# sensorCorrente_rev1_0.net
KiCad netlist of a schematic drawn in EAGLE
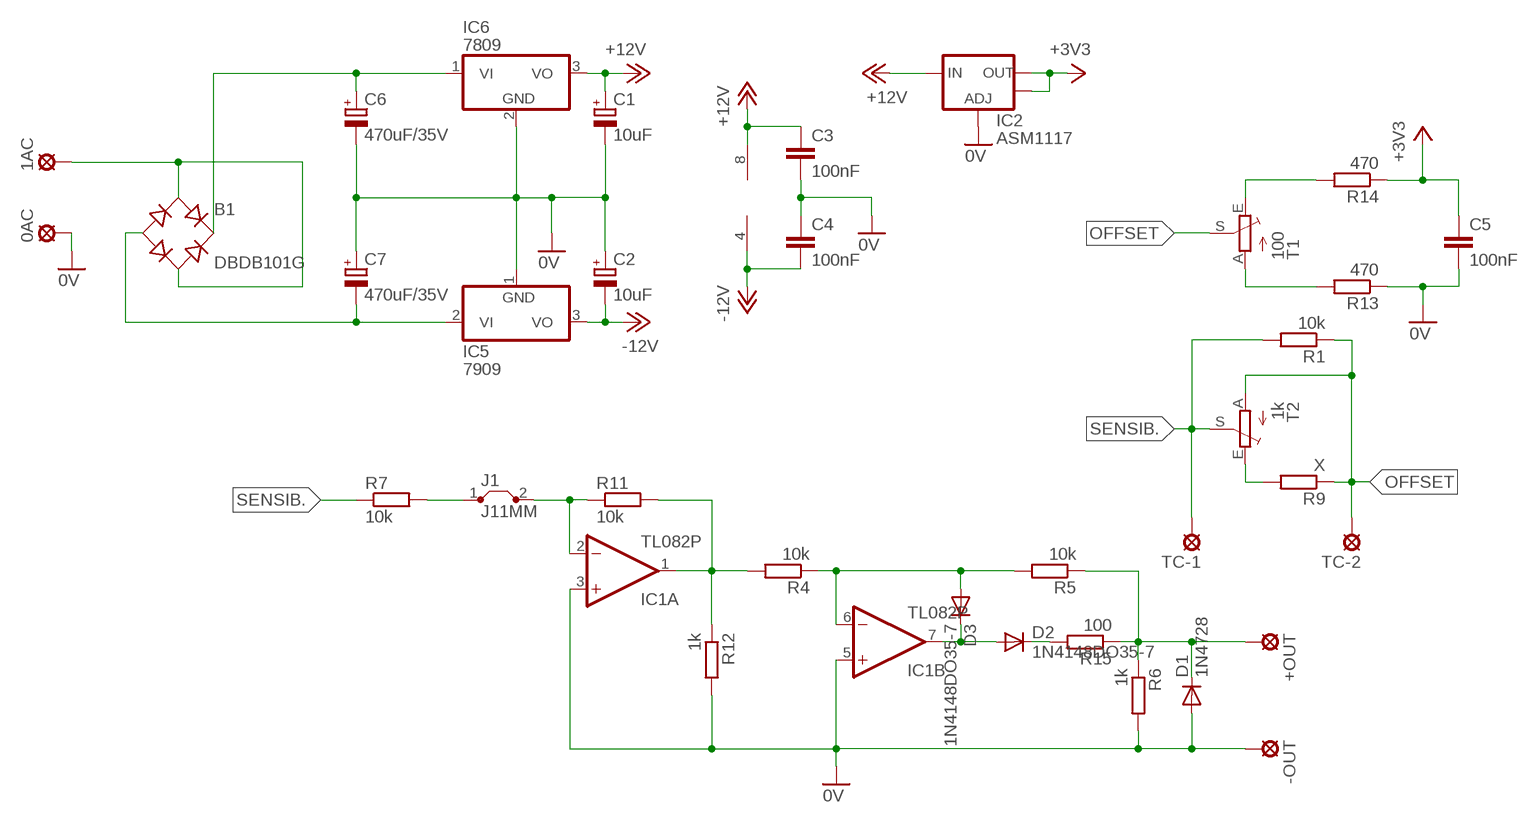
[diagram p0: schematic, sheet 1]

(export (version "E")
  (design (tool "Eeschema 10.0.6"))
  (components
    (comp (ref "+OUT")
      (value "+D")
      (footprint "eagle-import:LSP10")
      (libsource (lib "eagle-import") (part "LSP10"))
    )
    (comp (ref "-OUT")
      (value "0V")
      (footprint "eagle-import:LSP10")
      (libsource (lib "eagle-import") (part "LSP10"))
    )
    (comp (ref "0AC")
      (value "0V")
      (footprint "eagle-import:LSP10")
      (libsource (lib "eagle-import") (part "LSP10"))
    )
    (comp (ref "1AC")
      (value "AC")
      (footprint "eagle-import:LSP10")
      (libsource (lib "eagle-import") (part "LSP10"))
    )
    (comp (ref "B1")
      (value "DBDB101G")
      (footprint "eagle-import:DB")
      (libsource (lib "eagle-import") (part "DB?GDB101"))
    )
    (comp (ref "C1")
      (value "10uF")
      (footprint "eagle-import:E2,5-7")
      (libsource (lib "eagle-import") (part "CPOL-EUE2.5-7"))
    )
    (comp (ref "C2")
      (value "10uF")
      (footprint "eagle-import:E2,5-7")
      (libsource (lib "eagle-import") (part "CPOL-EUE2.5-7"))
    )
    (comp (ref "C3")
      (value "100nF")
      (footprint "eagle-import:C050-024X044")
      (libsource (lib "eagle-import") (part "C-EU050-024X044"))
    )
    (comp (ref "C4")
      (value "100nF")
      (footprint "eagle-import:C050-024X044")
      (libsource (lib "eagle-import") (part "C-EU050-024X044"))
    )
    (comp (ref "C5")
      (value "100nF")
      (footprint "eagle-import:C050-024X044")
      (libsource (lib "eagle-import") (part "C-EU050-024X044"))
    )
    (comp (ref "C6")
      (value "470uF/35V")
      (footprint "eagle-import:E3,5-10")
      (libsource (lib "eagle-import") (part "CPOL-EUE3.5-10"))
    )
    (comp (ref "C7")
      (value "470uF/35V")
      (footprint "eagle-import:E3,5-10")
      (libsource (lib "eagle-import") (part "CPOL-EUE3.5-10"))
    )
    (comp (ref "D1")
      (value "1N4728")
      (footprint "eagle-import:DO35-7")
      (libsource (lib "eagle-import") (part "1N4148DO35-7"))
    )
    (comp (ref "D2")
      (value "1N4148DO35-7")
      (footprint "eagle-import:DO35-7")
      (libsource (lib "eagle-import") (part "1N4148DO35-7"))
    )
    (comp (ref "D3")
      (value "1N4148DO35-7")
      (footprint "eagle-import:DO35-7")
      (libsource (lib "eagle-import") (part "1N4148DO35-7"))
    )
    (comp (ref "IC1")
      (value "TL082P")
      (footprint "eagle-import:DIL08")
      (libsource (lib "eagle-import") (part "TL082P"))
    )
    (comp (ref "IC2")
      (value "ASM1117")
      (footprint "eagle-import:SOT223")
      (libsource (lib "eagle-import") (part "V_REG_LM1117SOT223"))
    )
    (comp (ref "IC5")
      (value "7909")
      (footprint "eagle-import:TO220V")
      (libsource (lib "eagle-import") (part "7912"))
    )
    (comp (ref "IC6")
      (value "7809")
      (footprint "eagle-import:TO220V")
      (libsource (lib "eagle-import") (part "78TV12"))
    )
    (comp (ref "J1")
      (value "J11MM")
      (footprint "eagle-import:11")
      (libsource (lib "eagle-import") (part "J11MM"))
    )
    (comp (ref "R1")
      (value "10k")
      (footprint "eagle-import:0204_7")
      (libsource (lib "eagle-import") (part "R-EU_0204/7"))
    )
    (comp (ref "R4")
      (value "10k")
      (footprint "eagle-import:0204_7")
      (libsource (lib "eagle-import") (part "R-EU_0204/7"))
    )
    (comp (ref "R5")
      (value "10k")
      (footprint "eagle-import:0204_10")
      (libsource (lib "eagle-import") (part "R-EU_0204/10"))
    )
    (comp (ref "R6")
      (value "1k")
      (footprint "eagle-import:0204_7")
      (libsource (lib "eagle-import") (part "R-EU_0204/7"))
    )
    (comp (ref "R7")
      (value "10k")
      (footprint "eagle-import:0204_7")
      (libsource (lib "eagle-import") (part "R-EU_0204/7"))
    )
    (comp (ref "R9")
      (value "X")
      (footprint "eagle-import:0204_7")
      (libsource (lib "eagle-import") (part "R-EU_0204/7"))
    )
    (comp (ref "R11")
      (value "10k")
      (footprint "eagle-import:0204_7")
      (libsource (lib "eagle-import") (part "R-EU_0204/7"))
    )
    (comp (ref "R12")
      (value "1k")
      (footprint "eagle-import:0204_7")
      (libsource (lib "eagle-import") (part "R-EU_0204/7"))
    )
    (comp (ref "R13")
      (value "470")
      (footprint "eagle-import:0204_7")
      (libsource (lib "eagle-import") (part "R-EU_0204/7"))
    )
    (comp (ref "R14")
      (value "470")
      (footprint "eagle-import:0204_7")
      (libsource (lib "eagle-import") (part "R-EU_0204/7"))
    )
    (comp (ref "R15")
      (value "100")
      (footprint "eagle-import:0204_7")
      (libsource (lib "eagle-import") (part "R-EU_0204/7"))
    )
    (comp (ref "T1")
      (value "100")
      (footprint "eagle-import:CA6V")
      (libsource (lib "eagle-import") (part "TRIM_EU-CA6V"))
    )
    (comp (ref "T2")
      (value "1k")
      (footprint "eagle-import:CA6V")
      (libsource (lib "eagle-import") (part "TRIM_EU-CA6V"))
    )
    (comp (ref "TC-1")
      (value "AC")
      (footprint "eagle-import:LSP10")
      (libsource (lib "eagle-import") (part "LSP10"))
    )
    (comp (ref "TC-2")
      (value "AC")
      (footprint "eagle-import:LSP10")
      (libsource (lib "eagle-import") (part "LSP10"))
    )
  )
  (nets
    (net (code "1") (name "+3V3") (class "Default")
      (node (ref "C5") (pin "1") (pinfunction "1_1") (pintype "passive"))
      (node (ref "IC2") (pin "2") (pinfunction "OUT_2") (pintype "output"))
      (node (ref "IC2") (pin "4") (pinfunction "OUT_4") (pintype "output"))
      (node (ref "R14") (pin "1") (pinfunction "1_1") (pintype "passive"))
    )
    (net (code "2") (name "+12V") (class "Default")
      (node (ref "C1") (pin "+") (pinfunction "+_+") (pintype "passive"))
      (node (ref "C3") (pin "1") (pinfunction "1_1") (pintype "passive"))
      (node (ref "IC1") (pin "8") (pinfunction "V+_8") (pintype "power_in"))
      (node (ref "IC2") (pin "3") (pinfunction "IN_3") (pintype "input"))
      (node (ref "IC6") (pin "3") (pinfunction "VO_3") (pintype "passive"))
    )
    (net (code "3") (name "-12V") (class "Default")
      (node (ref "C2") (pin "-") (pinfunction "-_-") (pintype "passive"))
      (node (ref "C4") (pin "2") (pinfunction "2_2") (pintype "passive"))
      (node (ref "IC1") (pin "4") (pinfunction "V-_4") (pintype "power_in"))
      (node (ref "IC5") (pin "3") (pinfunction "VO_3") (pintype "passive"))
    )
    (net (code "4") (name "0V") (class "Default")
      (node (ref "-OUT") (pin "MP") (pinfunction "MP_MP") (pintype "passive"))
      (node (ref "0AC") (pin "MP") (pinfunction "MP_MP") (pintype "passive"))
      (node (ref "C1") (pin "-") (pinfunction "-_-") (pintype "passive"))
      (node (ref "C2") (pin "+") (pinfunction "+_+") (pintype "passive"))
      (node (ref "C3") (pin "2") (pinfunction "2_2") (pintype "passive"))
      (node (ref "C4") (pin "1") (pinfunction "1_1") (pintype "passive"))
      (node (ref "C5") (pin "2") (pinfunction "2_2") (pintype "passive"))
      (node (ref "C6") (pin "-") (pinfunction "-_-") (pintype "passive"))
      (node (ref "C7") (pin "+") (pinfunction "+_+") (pintype "passive"))
      (node (ref "D1") (pin "A") (pinfunction "A_A") (pintype "passive"))
      (node (ref "IC1") (pin "3") (pinfunction "+IN_3") (pintype "input"))
      (node (ref "IC1") (pin "5") (pinfunction "+IN_5") (pintype "input"))
      (node (ref "IC2") (pin "1") (pinfunction "ADJ_1") (pintype "input"))
      (node (ref "IC5") (pin "1") (pinfunction "GND_1") (pintype "passive"))
      (node (ref "IC6") (pin "2") (pinfunction "GND_2") (pintype "passive"))
      (node (ref "R12") (pin "2") (pinfunction "2_2") (pintype "passive"))
      (node (ref "R13") (pin "1") (pinfunction "1_1") (pintype "passive"))
      (node (ref "R6") (pin "2") (pinfunction "2_2") (pintype "passive"))
    )
    (net (code "5") (name "Net-(+OUT-PadMP)") (class "Default")
      (node (ref "+OUT") (pin "MP") (pinfunction "MP_MP") (pintype "passive"))
      (node (ref "D1") (pin "C") (pinfunction "C_C") (pintype "passive"))
      (node (ref "R15") (pin "1") (pinfunction "1_1") (pintype "passive"))
      (node (ref "R5") (pin "1") (pinfunction "1_1") (pintype "passive"))
      (node (ref "R6") (pin "1") (pinfunction "1_1") (pintype "passive"))
    )
    (net (code "6") (name "Net-(1AC-PadMP)") (class "Default")
      (node (ref "1AC") (pin "MP") (pinfunction "MP_MP") (pintype "passive"))
      (node (ref "B1") (pin "AC1") (pinfunction "AC1_AC1") (pintype "passive"))
      (node (ref "B1") (pin "AC2") (pinfunction "AC2_AC2") (pintype "passive"))
    )
    (net (code "7") (name "Net-(D2-PadC)") (class "Default")
      (node (ref "D2") (pin "C") (pinfunction "C_C") (pintype "passive"))
      (node (ref "R15") (pin "2") (pinfunction "2_2") (pintype "passive"))
    )
    (net (code "8") (name "Net-(IC1A--IN)") (class "Default")
      (node (ref "IC1") (pin "2") (pinfunction "-IN_2") (pintype "input"))
      (node (ref "J1") (pin "2") (pinfunction "2_2") (pintype "passive"))
      (node (ref "R11") (pin "1") (pinfunction "1_1") (pintype "passive"))
    )
    (net (code "9") (name "Net-(IC1A-OUT)") (class "Default")
      (node (ref "IC1") (pin "1") (pinfunction "OUT_1") (pintype "output"))
      (node (ref "R11") (pin "2") (pinfunction "2_2") (pintype "passive"))
      (node (ref "R12") (pin "1") (pinfunction "1_1") (pintype "passive"))
      (node (ref "R4") (pin "2") (pinfunction "2_2") (pintype "passive"))
    )
    (net (code "10") (name "Net-(IC1B--IN)") (class "Default")
      (node (ref "D3") (pin "A") (pinfunction "A_A") (pintype "passive"))
      (node (ref "IC1") (pin "6") (pinfunction "-IN_6") (pintype "input"))
      (node (ref "R4") (pin "1") (pinfunction "1_1") (pintype "passive"))
      (node (ref "R5") (pin "2") (pinfunction "2_2") (pintype "passive"))
    )
    (net (code "11") (name "Net-(IC1B-OUT)") (class "Default")
      (node (ref "D2") (pin "A") (pinfunction "A_A") (pintype "passive"))
      (node (ref "D3") (pin "C") (pinfunction "C_C") (pintype "passive"))
      (node (ref "IC1") (pin "7") (pinfunction "OUT_7") (pintype "output"))
    )
    (net (code "12") (name "Net-(IC5-VI)") (class "Default")
      (node (ref "B1") (pin "-") (pinfunction "-_-") (pintype "passive"))
      (node (ref "C7") (pin "-") (pinfunction "-_-") (pintype "passive"))
      (node (ref "IC5") (pin "2") (pinfunction "VI_2") (pintype "input"))
    )
    (net (code "13") (name "Net-(IC6-VI)") (class "Default")
      (node (ref "B1") (pin "+") (pinfunction "+_+") (pintype "passive"))
      (node (ref "C6") (pin "+") (pinfunction "+_+") (pintype "passive"))
      (node (ref "IC6") (pin "1") (pinfunction "VI_1") (pintype "input"))
    )
    (net (code "14") (name "Net-(J1-Pad1)") (class "Default")
      (node (ref "J1") (pin "1") (pinfunction "1_1") (pintype "passive"))
      (node (ref "R7") (pin "2") (pinfunction "2_2") (pintype "passive"))
    )
    (net (code "15") (name "Net-(R9-Pad2)") (class "Default")
      (node (ref "R9") (pin "2") (pinfunction "2_2") (pintype "passive"))
      (node (ref "T2") (pin "E") (pinfunction "E_E") (pintype "passive"))
    )
    (net (code "16") (name "Net-(R13-Pad2)") (class "Default")
      (node (ref "R13") (pin "2") (pinfunction "2_2") (pintype "passive"))
      (node (ref "T1") (pin "A") (pinfunction "A_A") (pintype "passive"))
    )
    (net (code "17") (name "Net-(R14-Pad2)") (class "Default")
      (node (ref "R14") (pin "2") (pinfunction "2_2") (pintype "passive"))
      (node (ref "T1") (pin "E") (pinfunction "E_E") (pintype "passive"))
    )
    (net (code "18") (name "OFFSET") (class "Default")
      (node (ref "R1") (pin "1") (pinfunction "1_1") (pintype "passive"))
      (node (ref "R9") (pin "1") (pinfunction "1_1") (pintype "passive"))
      (node (ref "T1") (pin "S") (pinfunction "S_S") (pintype "passive"))
      (node (ref "T2") (pin "A") (pinfunction "A_A") (pintype "passive"))
      (node (ref "TC-2") (pin "MP") (pinfunction "MP_MP") (pintype "passive"))
    )
    (net (code "19") (name "SENSIB.") (class "Default")
      (node (ref "R1") (pin "2") (pinfunction "2_2") (pintype "passive"))
      (node (ref "R7") (pin "1") (pinfunction "1_1") (pintype "passive"))
      (node (ref "T2") (pin "S") (pinfunction "S_S") (pintype "passive"))
      (node (ref "TC-1") (pin "MP") (pinfunction "MP_MP") (pintype "passive"))
    )
  )
)
